# multiplexer.net
KiCad netlist of a schematic drawn in EAGLE
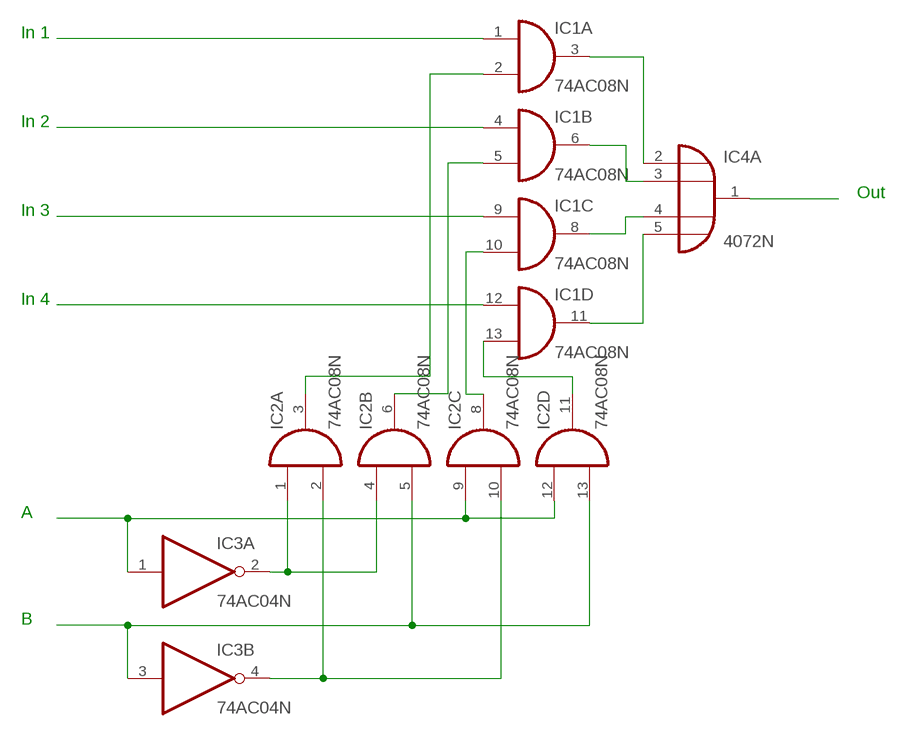
[diagram p0: schematic, sheet 1]

(export (version "E")
  (design (tool "Eeschema 10.0.6"))
  (components
    (comp (ref "IC1")
      (value "74AC08N")
      (footprint "eagle-import:DIL14")
      (libsource (lib "eagle-import") (part "7408NAC"))
    )
    (comp (ref "IC2")
      (value "74AC08N")
      (footprint "eagle-import:DIL14")
      (libsource (lib "eagle-import") (part "7408NAC"))
    )
    (comp (ref "IC3")
      (value "74AC04N")
      (footprint "eagle-import:DIL14")
      (libsource (lib "eagle-import") (part "7404NAC"))
    )
    (comp (ref "IC4")
      (value "4072N")
      (footprint "eagle-import:DIL14")
      (libsource (lib "eagle-import") (part "4072N"))
    )
  )
  (nets
    (net (code "1") (name "Net-(IC1A-I1)") (class "Default")
      (node (ref "IC1") (pin "2") (pinfunction "I1_2") (pintype "input"))
      (node (ref "IC2") (pin "3") (pinfunction "O_3") (pintype "output"))
    )
    (net (code "2") (name "Net-(IC1A-O)") (class "Default")
      (node (ref "IC1") (pin "3") (pinfunction "O_3") (pintype "output"))
      (node (ref "IC4") (pin "2") (pinfunction "I0_2") (pintype "input"))
    )
    (net (code "3") (name "Net-(IC1B-I1)") (class "Default")
      (node (ref "IC1") (pin "5") (pinfunction "I1_5") (pintype "input"))
      (node (ref "IC2") (pin "6") (pinfunction "O_6") (pintype "output"))
    )
    (net (code "4") (name "Net-(IC1B-O)") (class "Default")
      (node (ref "IC1") (pin "6") (pinfunction "O_6") (pintype "output"))
      (node (ref "IC4") (pin "3") (pinfunction "I1_3") (pintype "input"))
    )
    (net (code "5") (name "Net-(IC1C-I1)") (class "Default")
      (node (ref "IC1") (pin "10") (pinfunction "I1_10") (pintype "input"))
      (node (ref "IC2") (pin "8") (pinfunction "O_8") (pintype "output"))
    )
    (net (code "6") (name "Net-(IC1C-O)") (class "Default")
      (node (ref "IC1") (pin "8") (pinfunction "O_8") (pintype "output"))
      (node (ref "IC4") (pin "4") (pinfunction "I2_4") (pintype "input"))
    )
    (net (code "7") (name "Net-(IC1D-I1)") (class "Default")
      (node (ref "IC1") (pin "13") (pinfunction "I1_13") (pintype "input"))
      (node (ref "IC2") (pin "11") (pinfunction "O_11") (pintype "output"))
    )
    (net (code "8") (name "Net-(IC1D-O)") (class "Default")
      (node (ref "IC1") (pin "11") (pinfunction "O_11") (pintype "output"))
      (node (ref "IC4") (pin "5") (pinfunction "I3_5") (pintype "input"))
    )
    (net (code "9") (name "Net-(IC2A-I0)") (class "Default")
      (node (ref "IC2") (pin "1") (pinfunction "I0_1") (pintype "input"))
      (node (ref "IC2") (pin "4") (pinfunction "I0_4") (pintype "input"))
      (node (ref "IC3") (pin "2") (pinfunction "O_2") (pintype "output"))
    )
    (net (code "10") (name "Net-(IC2A-I1)") (class "Default")
      (node (ref "IC2") (pin "10") (pinfunction "I1_10") (pintype "input"))
      (node (ref "IC2") (pin "2") (pinfunction "I1_2") (pintype "input"))
      (node (ref "IC3") (pin "4") (pinfunction "O_4") (pintype "output"))
    )
    (net (code "11") (name "Net-(IC2B-I1)") (class "Default")
      (node (ref "IC2") (pin "13") (pinfunction "I1_13") (pintype "input"))
      (node (ref "IC2") (pin "5") (pinfunction "I1_5") (pintype "input"))
      (node (ref "IC3") (pin "3") (pinfunction "I_3") (pintype "input"))
    )
    (net (code "12") (name "Net-(IC2C-I0)") (class "Default")
      (node (ref "IC2") (pin "12") (pinfunction "I0_12") (pintype "input"))
      (node (ref "IC2") (pin "9") (pinfunction "I0_9") (pintype "input"))
      (node (ref "IC3") (pin "1") (pinfunction "I_1") (pintype "input"))
    )
    (net (code "13") (name "unconnected-(IC1A-I0-Pad1)") (class "Default")
      (node (ref "IC1") (pin "1") (pinfunction "I0_1") (pintype "input"))
    )
    (net (code "14") (name "unconnected-(IC1B-I0-Pad4)") (class "Default")
      (node (ref "IC1") (pin "4") (pinfunction "I0_4") (pintype "input"))
    )
    (net (code "15") (name "unconnected-(IC1C-I0-Pad9)") (class "Default")
      (node (ref "IC1") (pin "9") (pinfunction "I0_9") (pintype "input"))
    )
    (net (code "16") (name "unconnected-(IC1D-I0-Pad12)") (class "Default")
      (node (ref "IC1") (pin "12") (pinfunction "I0_12") (pintype "input"))
    )
    (net (code "17") (name "unconnected-(IC4A-O-Pad1)") (class "Default")
      (node (ref "IC4") (pin "1") (pinfunction "O_1") (pintype "output"))
    )
  )
)
